# MSP430_LEDS.net
KiCad netlist of a schematic drawn in EAGLE
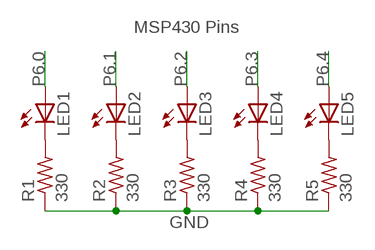
[diagram p0: schematic, sheet 1]

(export (version "E")
  (design (tool "Eeschema 10.0.6"))
  (components
    (comp (ref "LED1")
      (value "LED5MM")
      (footprint "eagle-import:LED5MM")
      (libsource (lib "eagle-import") (part "LED5MM"))
    )
    (comp (ref "LED2")
      (value "LED5MM")
      (footprint "eagle-import:LED5MM")
      (libsource (lib "eagle-import") (part "LED5MM"))
    )
    (comp (ref "LED3")
      (value "LED5MM")
      (footprint "eagle-import:LED5MM")
      (libsource (lib "eagle-import") (part "LED5MM"))
    )
    (comp (ref "LED4")
      (value "LED5MM")
      (footprint "eagle-import:LED5MM")
      (libsource (lib "eagle-import") (part "LED5MM"))
    )
    (comp (ref "LED5")
      (value "LED5MM")
      (footprint "eagle-import:LED5MM")
      (libsource (lib "eagle-import") (part "LED5MM"))
    )
    (comp (ref "R1")
      (value "330")
      (footprint "eagle-import:R0402")
      (libsource (lib "eagle-import") (part "R-US_R0402"))
    )
    (comp (ref "R2")
      (value "330")
      (footprint "eagle-import:R0402")
      (libsource (lib "eagle-import") (part "R-US_R0402"))
    )
    (comp (ref "R3")
      (value "330")
      (footprint "eagle-import:R0402")
      (libsource (lib "eagle-import") (part "R-US_R0402"))
    )
    (comp (ref "R4")
      (value "330")
      (footprint "eagle-import:R0402")
      (libsource (lib "eagle-import") (part "R-US_R0402"))
    )
    (comp (ref "R5")
      (value "330")
      (footprint "eagle-import:R0402")
      (libsource (lib "eagle-import") (part "R-US_R0402"))
    )
  )
  (nets
    (net (code "1") (name "/GND") (class "Default")
      (node (ref "R1") (pin "1") (pinfunction "1_1") (pintype "passive"))
      (node (ref "R2") (pin "1") (pinfunction "1_1") (pintype "passive"))
      (node (ref "R3") (pin "1") (pinfunction "1_1") (pintype "passive"))
      (node (ref "R4") (pin "1") (pinfunction "1_1") (pintype "passive"))
      (node (ref "R5") (pin "1") (pinfunction "1_1") (pintype "passive"))
    )
    (net (code "2") (name "/P6.0") (class "Default")
      (node (ref "LED1") (pin "A") (pinfunction "A_A") (pintype "passive"))
    )
    (net (code "3") (name "/P6.1") (class "Default")
      (node (ref "LED2") (pin "A") (pinfunction "A_A") (pintype "passive"))
    )
    (net (code "4") (name "/P6.2") (class "Default")
      (node (ref "LED3") (pin "A") (pinfunction "A_A") (pintype "passive"))
    )
    (net (code "5") (name "/P6.3") (class "Default")
      (node (ref "LED4") (pin "A") (pinfunction "A_A") (pintype "passive"))
    )
    (net (code "6") (name "/P6.4") (class "Default")
      (node (ref "LED5") (pin "A") (pinfunction "A_A") (pintype "passive"))
    )
    (net (code "7") (name "Net-(LED1-C)") (class "Default")
      (node (ref "LED1") (pin "K") (pinfunction "C_K") (pintype "passive"))
      (node (ref "R1") (pin "2") (pinfunction "2_2") (pintype "passive"))
    )
    (net (code "8") (name "Net-(LED2-C)") (class "Default")
      (node (ref "LED2") (pin "K") (pinfunction "C_K") (pintype "passive"))
      (node (ref "R2") (pin "2") (pinfunction "2_2") (pintype "passive"))
    )
    (net (code "9") (name "Net-(LED3-C)") (class "Default")
      (node (ref "LED3") (pin "K") (pinfunction "C_K") (pintype "passive"))
      (node (ref "R3") (pin "2") (pinfunction "2_2") (pintype "passive"))
    )
    (net (code "10") (name "Net-(LED4-C)") (class "Default")
      (node (ref "LED4") (pin "K") (pinfunction "C_K") (pintype "passive"))
      (node (ref "R4") (pin "2") (pinfunction "2_2") (pintype "passive"))
    )
    (net (code "11") (name "Net-(LED5-C)") (class "Default")
      (node (ref "LED5") (pin "K") (pinfunction "C_K") (pintype "passive"))
      (node (ref "R5") (pin "2") (pinfunction "2_2") (pintype "passive"))
    )
  )
)
